# STM32G431RBT6.net
KiCad netlist of a schematic drawn in Altium Designer
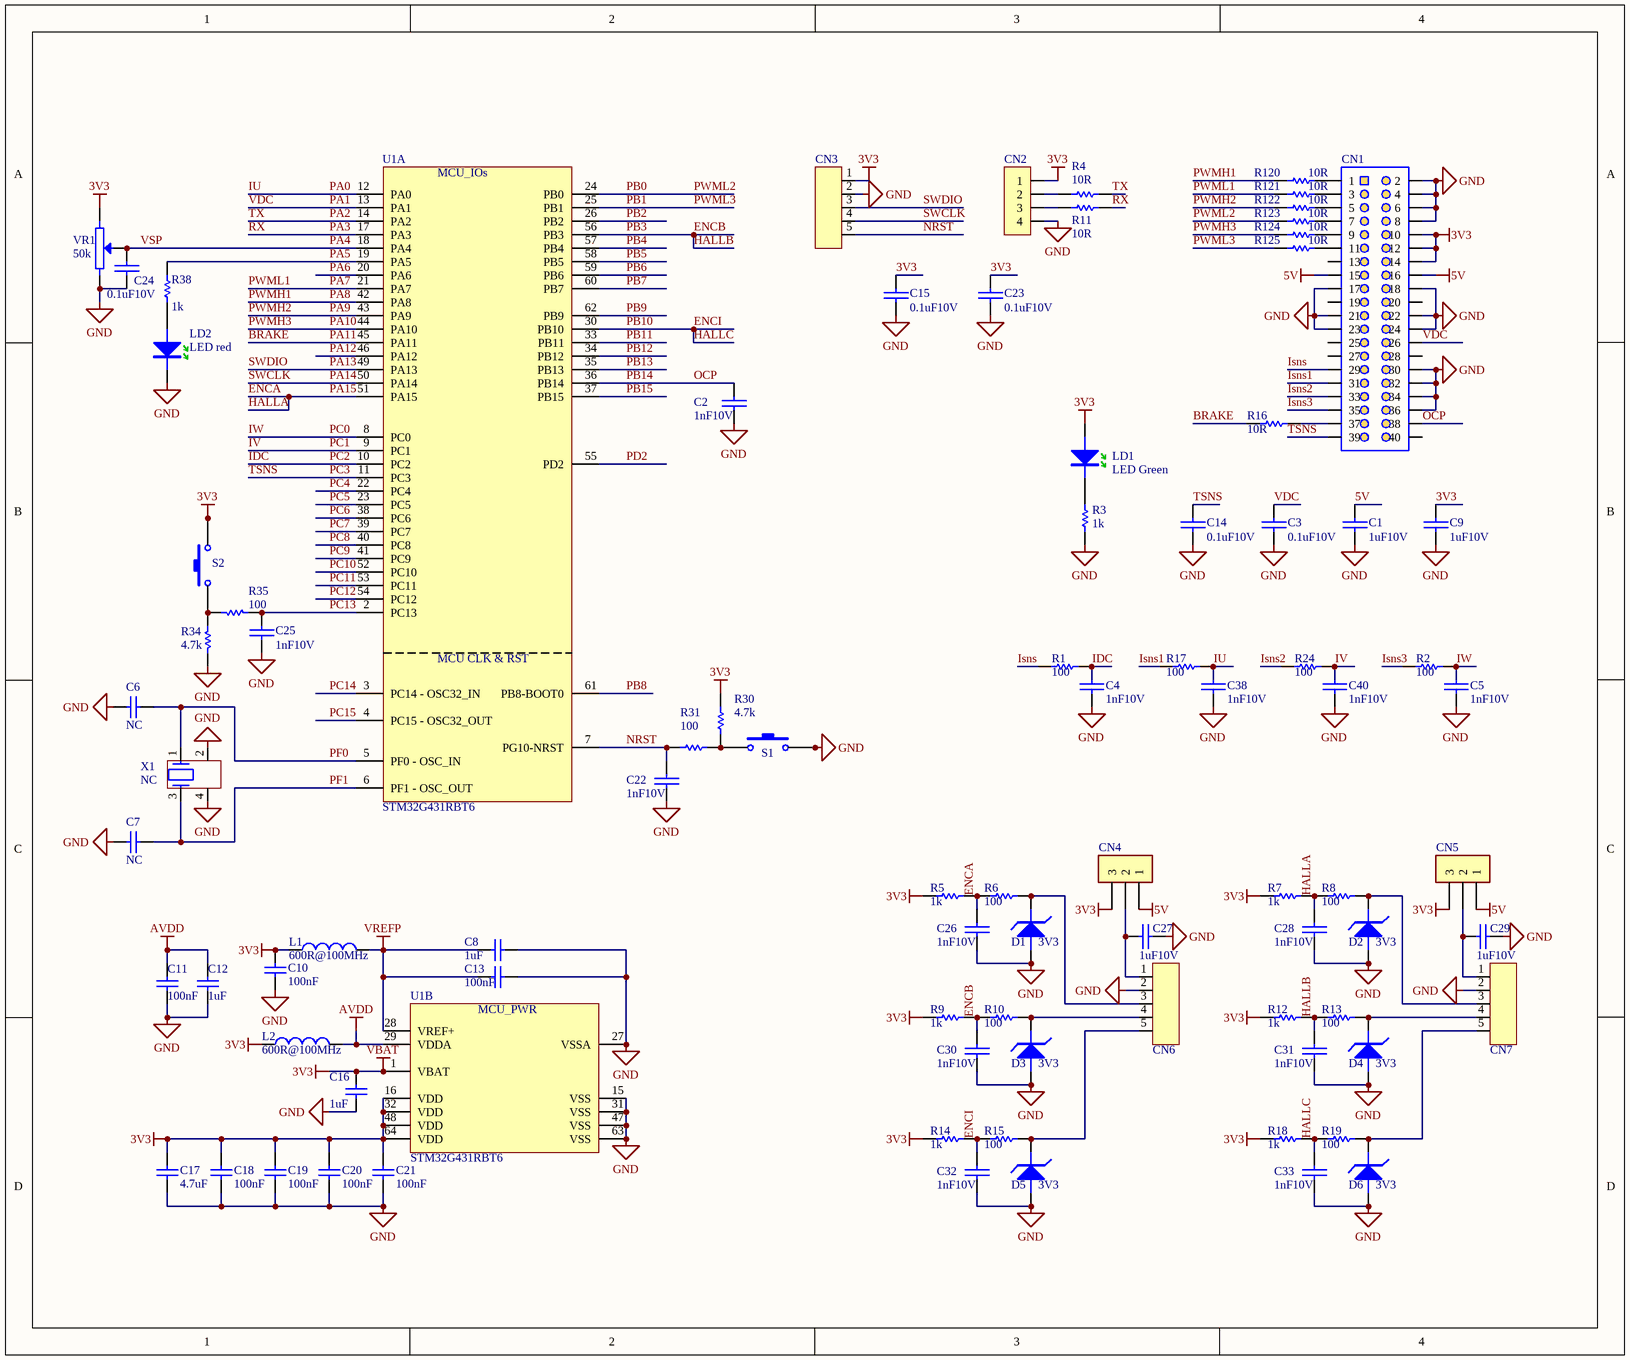
[diagram p0: STM32G431RBT6.SchDoc]

(export (version "E")
  (design (tool "Eeschema 10.0.6"))
  (components
    (comp (ref "C1")
      (value "UMK107AB7105KA-T")
      (footprint "CC0603")
      (fields
        (field (name "PART NUMBER") "C0603-10uF-50V-X7R-10%")
        (field (name "SCHDESCRIPT") "1uF10V")
        (field (name "VOLTAGE") "50")
        (field (name "TOLERANCE") "0.1")
      )
      (libsource (lib "EPC_Lib") (part "Capacitor-NonPolarized"))
    )
    (comp (ref "C2")
      (value "C0402C102J5GACTU")
      (footprint "CC0402")
      (fields
        (field (name "PART NUMBER") "C0402-1nF-50V-C0G/NP0-5%")
        (field (name "SCHDESCRIPT") "1nF10V")
        (field (name "EPC PART NUMBER") "C-0402-024")
        (field (name "VOLTAGE") "50")
      )
      (libsource (lib "EPC_Lib") (part "Capacitor-NonPolarized"))
    )
    (comp (ref "C3")
      (value "CC0402KRX7R8BB104")
      (footprint "CC0603")
      (fields
        (field (name "PART NUMBER") "C0402-100nF-25V-X7R-10%-Yaego")
        (field (name "SCHDESCRIPT") "0.1uF10V")
        (field (name "EPC PART NUMBER") "C-0402-088")
        (field (name "VOLTAGE") "25")
      )
      (libsource (lib "EPC_Lib") (part "Capacitor-NonPolarized"))
    )
    (comp (ref "C4")
      (value "C0402C102J5GACTU")
      (footprint "CC0402")
      (fields
        (field (name "PART NUMBER") "C0402-1nF-50V-C0G/NP0-5%")
        (field (name "SCHDESCRIPT") "1nF10V")
        (field (name "EPC PART NUMBER") "C-0402-024")
        (field (name "VOLTAGE") "50")
      )
      (libsource (lib "EPC_Lib") (part "Capacitor-NonPolarized"))
    )
    (comp (ref "C5")
      (value "C0402C102J5GACTU")
      (footprint "CC0402")
      (fields
        (field (name "PART NUMBER") "C0402-1nF-50V-C0G/NP0-5%")
        (field (name "SCHDESCRIPT") "1nF10V")
        (field (name "EPC PART NUMBER") "C-0402-024")
        (field (name "VOLTAGE") "50")
      )
      (libsource (lib "EPC_Lib") (part "Capacitor-NonPolarized"))
    )
    (comp (ref "C6")
      (value "NC")
      (footprint "CC0402")
      (description "Capacitor, MLCC, 6.8pF, 50V, NPO, +-0.25pF, 0402, T=0.5mm")
      (fields
        (field (name "INTERNAL_PART_NUMBER") "MCD-00674")
        (field (name "MANUFACTURER_PART_NUMBER") "CC0402CRNPO9BN6R8")
        (field (name "PROVIDED_BY") "SUBCO")
      )
      (libsource (lib "MCD_PARTS_database") (part "Capacitor"))
    )
    (comp (ref "C7")
      (value "NC")
      (footprint "CC0402")
      (description "Capacitor, MLCC, 6.8pF, 50V, NPO, +-0.25pF, 0402, T=0.5mm")
      (fields
        (field (name "INTERNAL_PART_NUMBER") "MCD-00674")
        (field (name "MANUFACTURER_PART_NUMBER") "CC0402CRNPO9BN6R8")
        (field (name "PROVIDED_BY") "SUBCO")
      )
      (libsource (lib "MCD_PARTS_database") (part "Capacitor"))
    )
    (comp (ref "C8")
      (value "1uF")
      (footprint "CC0603")
      (description "Capacitor, MLCC, 1uF, 16V, X5R, 10%, 0603, T=0,8mm")
      (fields
        (field (name "INTERNAL_PART_NUMBER") "MCD-00010")
        (field (name "MANUFACTURER_PART_NUMBER") "CC0603KRX5R7BB105")
        (field (name "PROVIDED_BY") "Subcon")
      )
      (libsource (lib "MCD_PARTS_database") (part "Capacitor"))
    )
    (comp (ref "C9")
      (value "UMK107AB7105KA-T")
      (footprint "CC0603")
      (fields
        (field (name "PART NUMBER") "C0603-10uF-50V-X7R-10%")
        (field (name "SCHDESCRIPT") "1uF10V")
        (field (name "VOLTAGE") "50")
        (field (name "TOLERANCE") "0.1")
      )
      (libsource (lib "EPC_Lib") (part "Capacitor-NonPolarized"))
    )
    (comp (ref "C10")
      (value "100nF")
      (footprint "CC0402")
      (description "Capacitor, MLCC, 100nF, 16V, X7R, 10%, 0402, T=0,5mm")
      (fields
        (field (name "INTERNAL_PART_NUMBER") "MCD-00102")
        (field (name "MANUFACTURER_PART_NUMBER") "CC0402KRX7R7BB104")
        (field (name "PROVIDED_BY") "Subcon")
      )
      (libsource (lib "MCD_PARTS_database") (part "Capacitor"))
    )
    (comp (ref "C11")
      (value "100nF")
      (footprint "CC0402")
      (description "Capacitor, MLCC, 100nF, 16V, X7R, 10%, 0402, T=0,5mm")
      (fields
        (field (name "INTERNAL_PART_NUMBER") "MCD-00102")
        (field (name "MANUFACTURER_PART_NUMBER") "CC0402KRX7R7BB104")
        (field (name "PROVIDED_BY") "Subcon")
      )
      (libsource (lib "MCD_PARTS_database") (part "Capacitor"))
    )
    (comp (ref "C12")
      (value "1uF")
      (footprint "CC0603")
      (description "Capacitor, MLCC, 1uF, 16V, X5R, 10%, 0603, T=0,8mm")
      (fields
        (field (name "INTERNAL_PART_NUMBER") "MCD-00010")
        (field (name "MANUFACTURER_PART_NUMBER") "CC0603KRX5R7BB105")
        (field (name "PROVIDED_BY") "Subcon")
      )
      (libsource (lib "MCD_PARTS_database") (part "Capacitor"))
    )
    (comp (ref "C13")
      (value "100nF")
      (footprint "CC0402")
      (description "Capacitor, MLCC, 100nF, 16V, X7R, 10%, 0402, T=0,5mm")
      (fields
        (field (name "INTERNAL_PART_NUMBER") "MCD-00102")
        (field (name "MANUFACTURER_PART_NUMBER") "CC0402KRX7R7BB104")
        (field (name "PROVIDED_BY") "Subcon")
      )
      (libsource (lib "MCD_PARTS_database") (part "Capacitor"))
    )
    (comp (ref "C14")
      (value "CC0402KRX7R8BB104")
      (footprint "CC0603")
      (fields
        (field (name "PART NUMBER") "C0402-100nF-25V-X7R-10%-Yaego")
        (field (name "SCHDESCRIPT") "0.1uF10V")
        (field (name "EPC PART NUMBER") "C-0402-088")
        (field (name "VOLTAGE") "25")
      )
      (libsource (lib "EPC_Lib") (part "Capacitor-NonPolarized"))
    )
    (comp (ref "C15")
      (value "CC0402KRX7R8BB104")
      (footprint "CC0402")
      (fields
        (field (name "PART NUMBER") "C0402-100nF-25V-X7R-10%-Yaego")
        (field (name "SCHDESCRIPT") "0.1uF10V")
        (field (name "EPC PART NUMBER") "C-0402-088")
        (field (name "VOLTAGE") "25")
      )
      (libsource (lib "EPC_Lib") (part "Capacitor-NonPolarized"))
    )
    (comp (ref "C16")
      (value "1uF")
      (footprint "CC0603")
      (description "Capacitor, MLCC, 1uF, 16V, X5R, 10%, 0603, T=0,8mm")
      (fields
        (field (name "INTERNAL_PART_NUMBER") "MCD-00010")
        (field (name "MANUFACTURER_PART_NUMBER") "CC0603KRX5R7BB105")
        (field (name "PROVIDED_BY") "Subcon")
      )
      (libsource (lib "MCD_PARTS_database") (part "Capacitor"))
    )
    (comp (ref "C17")
      (value "4.7uF")
      (footprint "CC0603")
      (description "Capacitor, MLCC, 4.7uF, 16V, X5R, 10%, 0603, T=0.8mm")
      (fields
        (field (name "INTERNAL_PART_NUMBER") "MCD-00009")
        (field (name "MANUFACTURER_PART_NUMBER") "CC0603KRX5R7BB475")
        (field (name "PROVIDED_BY") "subcon")
      )
      (libsource (lib "MCD_PARTS_database") (part "Capacitor"))
    )
    (comp (ref "C18")
      (value "100nF")
      (footprint "CC0402")
      (description "Capacitor, MLCC, 100nF, 16V, X7R, 10%, 0402, T=0,5mm")
      (fields
        (field (name "INTERNAL_PART_NUMBER") "MCD-00102")
        (field (name "MANUFACTURER_PART_NUMBER") "CC0402KRX7R7BB104")
        (field (name "PROVIDED_BY") "Subcon")
      )
      (libsource (lib "MCD_PARTS_database") (part "Capacitor"))
    )
    (comp (ref "C19")
      (value "100nF")
      (footprint "CC0402")
      (description "Capacitor, MLCC, 100nF, 16V, X7R, 10%, 0402, T=0,5mm")
      (fields
        (field (name "INTERNAL_PART_NUMBER") "MCD-00102")
        (field (name "MANUFACTURER_PART_NUMBER") "CC0402KRX7R7BB104")
        (field (name "PROVIDED_BY") "Subcon")
      )
      (libsource (lib "MCD_PARTS_database") (part "Capacitor"))
    )
    (comp (ref "C20")
      (value "100nF")
      (footprint "CC0402")
      (description "Capacitor, MLCC, 100nF, 16V, X7R, 10%, 0402, T=0,5mm")
      (fields
        (field (name "INTERNAL_PART_NUMBER") "MCD-00102")
        (field (name "MANUFACTURER_PART_NUMBER") "CC0402KRX7R7BB104")
        (field (name "PROVIDED_BY") "Subcon")
      )
      (libsource (lib "MCD_PARTS_database") (part "Capacitor"))
    )
    (comp (ref "C21")
      (value "100nF")
      (footprint "CC0402")
      (description "Capacitor, MLCC, 100nF, 16V, X7R, 10%, 0402, T=0,5mm")
      (fields
        (field (name "INTERNAL_PART_NUMBER") "MCD-00102")
        (field (name "MANUFACTURER_PART_NUMBER") "CC0402KRX7R7BB104")
        (field (name "PROVIDED_BY") "Subcon")
      )
      (libsource (lib "MCD_PARTS_database") (part "Capacitor"))
    )
    (comp (ref "C22")
      (value "CC0402KRX7R8BB104")
      (footprint "CC0402")
      (fields
        (field (name "PART NUMBER") "C0402-100nF-25V-X7R-10%-Yaego")
        (field (name "SCHDESCRIPT") "1nF10V")
        (field (name "EPC PART NUMBER") "C-0402-088")
        (field (name "VOLTAGE") "25")
      )
      (libsource (lib "EPC_Lib") (part "Capacitor-NonPolarized"))
    )
    (comp (ref "C23")
      (value "CC0402KRX7R8BB104")
      (footprint "CC0402")
      (fields
        (field (name "PART NUMBER") "C0402-100nF-25V-X7R-10%-Yaego")
        (field (name "SCHDESCRIPT") "0.1uF10V")
        (field (name "EPC PART NUMBER") "C-0402-088")
        (field (name "VOLTAGE") "25")
      )
      (libsource (lib "EPC_Lib") (part "Capacitor-NonPolarized"))
    )
    (comp (ref "C24")
      (value "CC0402KRX7R8BB104")
      (footprint "CC0402")
      (fields
        (field (name "PART NUMBER") "C0402-100nF-25V-X7R-10%-Yaego")
        (field (name "SCHDESCRIPT") "0.1uF10V")
        (field (name "EPC PART NUMBER") "C-0402-088")
        (field (name "VOLTAGE") "25")
      )
      (libsource (lib "EPC_Lib") (part "Capacitor-NonPolarized"))
    )
    (comp (ref "C25")
      (value "CC0402KRX7R8BB104")
      (footprint "CC0402")
      (fields
        (field (name "PART NUMBER") "C0402-100nF-25V-X7R-10%-Yaego")
        (field (name "SCHDESCRIPT") "1nF10V")
        (field (name "EPC PART NUMBER") "C-0402-088")
        (field (name "VOLTAGE") "25")
      )
      (libsource (lib "EPC_Lib") (part "Capacitor-NonPolarized"))
    )
    (comp (ref "C26")
      (value "C0402C102J5GACTU")
      (footprint "CC0402")
      (fields
        (field (name "PART NUMBER") "C0402-1nF-50V-C0G/NP0-5%")
        (field (name "SCHDESCRIPT") "1nF10V")
        (field (name "EPC PART NUMBER") "C-0402-024")
        (field (name "VOLTAGE") "50")
      )
      (libsource (lib "EPC_Lib") (part "Capacitor-NonPolarized"))
    )
    (comp (ref "C27")
      (value "1uF10V")
      (footprint "0603C")
      (fields (field (name "MFG") "TDK"))
      (libsource (lib "Personal") (part "CAP0603"))
    )
    (comp (ref "C28")
      (value "C0402C102J5GACTU")
      (footprint "CC0402")
      (fields
        (field (name "PART NUMBER") "C0402-1nF-50V-C0G/NP0-5%")
        (field (name "SCHDESCRIPT") "1nF10V")
        (field (name "EPC PART NUMBER") "C-0402-024")
        (field (name "VOLTAGE") "50")
      )
      (libsource (lib "EPC_Lib") (part "Capacitor-NonPolarized"))
    )
    (comp (ref "C29")
      (value "1uF10V")
      (footprint "0603C")
      (fields (field (name "MFG") "TDK"))
      (libsource (lib "Personal") (part "CAP0603"))
    )
    (comp (ref "C30")
      (value "C0402C102J5GACTU")
      (footprint "CC0402")
      (fields
        (field (name "PART NUMBER") "C0402-1nF-50V-C0G/NP0-5%")
        (field (name "SCHDESCRIPT") "1nF10V")
        (field (name "EPC PART NUMBER") "C-0402-024")
        (field (name "VOLTAGE") "50")
      )
      (libsource (lib "EPC_Lib") (part "Capacitor-NonPolarized"))
    )
    (comp (ref "C31")
      (value "C0402C102J5GACTU")
      (footprint "CC0402")
      (fields
        (field (name "PART NUMBER") "C0402-1nF-50V-C0G/NP0-5%")
        (field (name "SCHDESCRIPT") "1nF10V")
        (field (name "EPC PART NUMBER") "C-0402-024")
        (field (name "VOLTAGE") "50")
      )
      (libsource (lib "EPC_Lib") (part "Capacitor-NonPolarized"))
    )
    (comp (ref "C32")
      (value "C0402C102J5GACTU")
      (footprint "CC0402")
      (fields
        (field (name "PART NUMBER") "C0402-1nF-50V-C0G/NP0-5%")
        (field (name "SCHDESCRIPT") "1nF10V")
        (field (name "EPC PART NUMBER") "C-0402-024")
        (field (name "VOLTAGE") "50")
      )
      (libsource (lib "EPC_Lib") (part "Capacitor-NonPolarized"))
    )
    (comp (ref "C33")
      (value "C0402C102J5GACTU")
      (footprint "CC0402")
      (fields
        (field (name "PART NUMBER") "C0402-1nF-50V-C0G/NP0-5%")
        (field (name "SCHDESCRIPT") "1nF10V")
        (field (name "EPC PART NUMBER") "C-0402-024")
        (field (name "VOLTAGE") "50")
      )
      (libsource (lib "EPC_Lib") (part "Capacitor-NonPolarized"))
    )
    (comp (ref "C38")
      (value "C0402C102J5GACTU")
      (footprint "CC0402")
      (fields
        (field (name "PART NUMBER") "C0402-1nF-50V-C0G/NP0-5%")
        (field (name "SCHDESCRIPT") "1nF10V")
        (field (name "EPC PART NUMBER") "C-0402-024")
        (field (name "VOLTAGE") "50")
      )
      (libsource (lib "EPC_Lib") (part "Capacitor-NonPolarized"))
    )
    (comp (ref "C40")
      (value "C0402C102J5GACTU")
      (footprint "CC0402")
      (fields
        (field (name "PART NUMBER") "C0402-1nF-50V-C0G/NP0-5%")
        (field (name "SCHDESCRIPT") "1nF10V")
        (field (name "EPC PART NUMBER") "C-0402-024")
        (field (name "VOLTAGE") "50")
      )
      (libsource (lib "EPC_Lib") (part "Capacitor-NonPolarized"))
    )
    (comp (ref "CN1")
      (value "SFH11-PBPC-D17-ST-BK")
      (footprint "HDR_F10_D17_TH_VT_Pol_Bot")
      (description "34pin Female Vertical polarized on BOTTOM")
      (fields (field (name "MFG") "Sullins"))
      (libsource (lib "ATSAME70N20B") (part "HDR_F_D17_VT"))
    )
    (comp (ref "CN2")
      (value "~")
      (footprint "HDR_M10_S4_TH_VT")
      (libsource (lib "SERVO_EPC23101_ATSAME70N20B") (part "PIN-1-4-254"))
    )
    (comp (ref "CN3") (value "2.54mm,5Pin") (footprint "PIN5") (libsource (lib "F030") (part "PIN-1-5-254")))
    (comp (ref "CN4")
      (value "~")
      (footprint "PIN3_2.54mm")
      (description "CN")
      (libsource (lib "*") (part "CN3"))
    )
    (comp (ref "CN5")
      (value "~")
      (footprint "PIN3_2.54mm")
      (description "CN")
      (libsource (lib "*") (part "CN3"))
    )
    (comp (ref "CN6") (value "2.54mm,5Pin") (footprint "PIN5") (libsource (lib "") (part "PIN-1-5-254_1")))
    (comp (ref "CN7") (value "2.54mm,5Pin") (footprint "PIN5") (libsource (lib "") (part "PIN-1-5-254_1")))
    (comp (ref "D1")
      (value "3V3")
      (footprint "1206D")
      (description "Diode Zener")
      (fields (field (name "MFG") "Diodes Inc."))
      (libsource (lib "Personal") (part "Diode Zener"))
    )
    (comp (ref "D2")
      (value "3V3")
      (footprint "1206D")
      (description "Diode Zener")
      (fields (field (name "MFG") "Diodes Inc."))
      (libsource (lib "Personal") (part "Diode Zener"))
    )
    (comp (ref "D3")
      (value "3V3")
      (footprint "1206D")
      (description "Diode Zener")
      (fields (field (name "MFG") "Diodes Inc."))
      (libsource (lib "Personal") (part "Diode Zener"))
    )
    (comp (ref "D4")
      (value "3V3")
      (footprint "1206D")
      (description "Diode Zener")
      (fields (field (name "MFG") "Diodes Inc."))
      (libsource (lib "Personal") (part "Diode Zener"))
    )
    (comp (ref "D5")
      (value "3V3")
      (footprint "1206D")
      (description "Diode Zener")
      (fields (field (name "MFG") "Diodes Inc."))
      (libsource (lib "Personal") (part "Diode Zener"))
    )
    (comp (ref "D6")
      (value "3V3")
      (footprint "1206D")
      (description "Diode Zener")
      (fields (field (name "MFG") "Diodes Inc."))
      (libsource (lib "Personal") (part "Diode Zener"))
    )
    (comp (ref "L1")
      (value "600R@100MHz")
      (footprint "RC0603")
      (description "SMD Chip ferrite bead, 600R@100MHz +/-25%, 350mA, 500mohm DC, 0603, T=0.8mm")
      (fields
        (field (name "INTERNAL_PART_NUMBER") "MCD-00047")
        (field (name "MANUFACTURER_PART_NUMBER") "FCM1608KF-601T03")
        (field (name "PROVIDED_BY") "SUBCO")
      )
      (libsource (lib "MCD_PARTS_database") (part "BEAD"))
    )
    (comp (ref "L2")
      (value "600R@100MHz")
      (footprint "RC0603")
      (description "SMD Chip ferrite bead, 600R@100MHz +/-25%, 350mA, 500mohm DC, 0603, T=0.8mm")
      (fields
        (field (name "INTERNAL_PART_NUMBER") "MCD-00047")
        (field (name "MANUFACTURER_PART_NUMBER") "FCM1608KF-601T03")
        (field (name "PROVIDED_BY") "SUBCO")
      )
      (libsource (lib "MCD_PARTS_database") (part "BEAD"))
    )
    (comp (ref "LD1")
      (value "LED Green")
      (footprint "D0603")
      (description "Green 570nm LED Indication - Discrete 2V 0603")
      (fields (field (name "MFG") "Wurth") (field (name "Comment") "150060VS75000"))
      (libsource (lib "Personal") (part "LED0603Gn"))
    )
    (comp (ref "LD2")
      (value "LED red")
      (footprint "D0603")
      (description "Green 570nm LED Indication - Discrete 2V 0603")
      (fields (field (name "MFG") "Wurth") (field (name "Comment") "150060VS75000"))
      (libsource (lib "Personal") (part "LED0603Gn"))
    )
    (comp (ref "R1")
      (value "ERJ-2RKF1001X")
      (footprint "RC0402")
      (fields
        (field (name "PART NUMBER") "R0402-1k-1%-0.1W-Thickfilm")
        (field (name "SCHDESCRIPT") "100")
        (field (name "EPC PART NUMBER") "R-0402-020")
        (field (name "TOLERANCE") "0.01")
      )
      (libsource (lib "EPC_Lib") (part "Resistor"))
    )
    (comp (ref "R2")
      (value "ERJ-2RKF1001X")
      (footprint "RC0402")
      (fields
        (field (name "PART NUMBER") "R0402-1k-1%-0.1W-Thickfilm")
        (field (name "SCHDESCRIPT") "100")
        (field (name "EPC PART NUMBER") "R-0402-020")
        (field (name "TOLERANCE") "0.01")
      )
      (libsource (lib "EPC_Lib") (part "Resistor"))
    )
    (comp (ref "R3")
      (value "ERJ-2RKF1001X")
      (footprint "RC0402")
      (fields
        (field (name "PART NUMBER") "R0402-1k-1%-0.1W-Thickfilm")
        (field (name "SCHDESCRIPT") "1k")
        (field (name "EPC PART NUMBER") "R-0402-020")
        (field (name "TOLERANCE") "0.01")
      )
      (libsource (lib "EPC_Lib") (part "Resistor"))
    )
    (comp (ref "R4")
      (value "ERJ-2RKF1001X")
      (footprint "RC0402")
      (fields
        (field (name "PART NUMBER") "R0402-1k-1%-0.1W-Thickfilm")
        (field (name "SCHDESCRIPT") "10R")
        (field (name "EPC PART NUMBER") "R-0402-020")
        (field (name "TOLERANCE") "0.01")
      )
      (libsource (lib "EPC_Lib") (part "Resistor"))
    )
    (comp (ref "R5")
      (value "ERJ-2RKF1001X")
      (footprint "RC0402")
      (fields
        (field (name "PART NUMBER") "R0402-1k-1%-0.1W-Thickfilm")
        (field (name "SCHDESCRIPT") "1k")
        (field (name "EPC PART NUMBER") "R-0402-020")
        (field (name "TOLERANCE") "0.01")
      )
      (libsource (lib "EPC_Lib") (part "Resistor"))
    )
    (comp (ref "R6")
      (value "ERJ-2RKF1001X")
      (footprint "RC0402")
      (fields
        (field (name "PART NUMBER") "R0402-1k-1%-0.1W-Thickfilm")
        (field (name "SCHDESCRIPT") "100")
        (field (name "EPC PART NUMBER") "R-0402-020")
        (field (name "TOLERANCE") "0.01")
      )
      (libsource (lib "EPC_Lib") (part "Resistor"))
    )
    (comp (ref "R7")
      (value "ERJ-2RKF1001X")
      (footprint "RC0402")
      (fields
        (field (name "PART NUMBER") "R0402-1k-1%-0.1W-Thickfilm")
        (field (name "SCHDESCRIPT") "1k")
        (field (name "EPC PART NUMBER") "R-0402-020")
        (field (name "TOLERANCE") "0.01")
      )
      (libsource (lib "EPC_Lib") (part "Resistor"))
    )
    (comp (ref "R8")
      (value "ERJ-2RKF1001X")
      (footprint "RC0402")
      (fields
        (field (name "PART NUMBER") "R0402-1k-1%-0.1W-Thickfilm")
        (field (name "SCHDESCRIPT") "100")
        (field (name "EPC PART NUMBER") "R-0402-020")
        (field (name "TOLERANCE") "0.01")
      )
      (libsource (lib "EPC_Lib") (part "Resistor"))
    )
    (comp (ref "R9")
      (value "ERJ-2RKF1001X")
      (footprint "RC0402")
      (fields
        (field (name "PART NUMBER") "R0402-1k-1%-0.1W-Thickfilm")
        (field (name "SCHDESCRIPT") "1k")
        (field (name "EPC PART NUMBER") "R-0402-020")
        (field (name "TOLERANCE") "0.01")
      )
      (libsource (lib "EPC_Lib") (part "Resistor"))
    )
    (comp (ref "R10")
      (value "ERJ-2RKF1001X")
      (footprint "RC0402")
      (fields
        (field (name "PART NUMBER") "R0402-1k-1%-0.1W-Thickfilm")
        (field (name "SCHDESCRIPT") "100")
        (field (name "EPC PART NUMBER") "R-0402-020")
        (field (name "TOLERANCE") "0.01")
      )
      (libsource (lib "EPC_Lib") (part "Resistor"))
    )
    (comp (ref "R11")
      (value "ERJ-2RKF1001X")
      (footprint "RC0402")
      (fields
        (field (name "PART NUMBER") "R0402-1k-1%-0.1W-Thickfilm")
        (field (name "SCHDESCRIPT") "10R")
        (field (name "EPC PART NUMBER") "R-0402-020")
        (field (name "TOLERANCE") "0.01")
      )
      (libsource (lib "EPC_Lib") (part "Resistor"))
    )
    (comp (ref "R12")
      (value "ERJ-2RKF1001X")
      (footprint "RC0402")
      (fields
        (field (name "PART NUMBER") "R0402-1k-1%-0.1W-Thickfilm")
        (field (name "SCHDESCRIPT") "1k")
        (field (name "EPC PART NUMBER") "R-0402-020")
        (field (name "TOLERANCE") "0.01")
      )
      (libsource (lib "EPC_Lib") (part "Resistor"))
    )
    (comp (ref "R13")
      (value "ERJ-2RKF1001X")
      (footprint "RC0402")
      (fields
        (field (name "PART NUMBER") "R0402-1k-1%-0.1W-Thickfilm")
        (field (name "SCHDESCRIPT") "100")
        (field (name "EPC PART NUMBER") "R-0402-020")
        (field (name "TOLERANCE") "0.01")
      )
      (libsource (lib "EPC_Lib") (part "Resistor"))
    )
    (comp (ref "R14")
      (value "ERJ-2RKF1001X")
      (footprint "RC0402")
      (fields
        (field (name "PART NUMBER") "R0402-1k-1%-0.1W-Thickfilm")
        (field (name "SCHDESCRIPT") "1k")
        (field (name "EPC PART NUMBER") "R-0402-020")
        (field (name "TOLERANCE") "0.01")
      )
      (libsource (lib "EPC_Lib") (part "Resistor"))
    )
    (comp (ref "R15")
      (value "ERJ-2RKF1001X")
      (footprint "RC0402")
      (fields
        (field (name "PART NUMBER") "R0402-1k-1%-0.1W-Thickfilm")
        (field (name "SCHDESCRIPT") "100")
        (field (name "EPC PART NUMBER") "R-0402-020")
        (field (name "TOLERANCE") "0.01")
      )
      (libsource (lib "EPC_Lib") (part "Resistor"))
    )
    (comp (ref "R16")
      (value "ERJ-2RKF10R0X")
      (footprint "RC0402")
      (fields
        (field (name "PART NUMBER") "R0402-10-1%-0.1W-ThickFilm")
        (field (name "SCHDESCRIPT") "10R")
        (field (name "EPC PART NUMBER") "R-0402-015")
        (field (name "TOLERANCE") "0.01")
      )
      (libsource (lib "EPC_Lib") (part "Resistor"))
    )
    (comp (ref "R17")
      (value "ERJ-2RKF1001X")
      (footprint "RC0402")
      (fields
        (field (name "PART NUMBER") "R0402-1k-1%-0.1W-Thickfilm")
        (field (name "SCHDESCRIPT") "100")
        (field (name "EPC PART NUMBER") "R-0402-020")
        (field (name "TOLERANCE") "0.01")
      )
      (libsource (lib "EPC_Lib") (part "Resistor"))
    )
    (comp (ref "R18")
      (value "ERJ-2RKF1001X")
      (footprint "RC0402")
      (fields
        (field (name "PART NUMBER") "R0402-1k-1%-0.1W-Thickfilm")
        (field (name "SCHDESCRIPT") "1k")
        (field (name "EPC PART NUMBER") "R-0402-020")
        (field (name "TOLERANCE") "0.01")
      )
      (libsource (lib "EPC_Lib") (part "Resistor"))
    )
    (comp (ref "R19")
      (value "ERJ-2RKF1001X")
      (footprint "RC0402")
      (fields
        (field (name "PART NUMBER") "R0402-1k-1%-0.1W-Thickfilm")
        (field (name "SCHDESCRIPT") "100")
        (field (name "EPC PART NUMBER") "R-0402-020")
        (field (name "TOLERANCE") "0.01")
      )
      (libsource (lib "EPC_Lib") (part "Resistor"))
    )
    (comp (ref "R24")
      (value "ERJ-2RKF1001X")
      (footprint "RC0402")
      (fields
        (field (name "PART NUMBER") "R0402-1k-1%-0.1W-Thickfilm")
        (field (name "SCHDESCRIPT") "100")
        (field (name "EPC PART NUMBER") "R-0402-020")
        (field (name "TOLERANCE") "0.01")
      )
      (libsource (lib "EPC_Lib") (part "Resistor"))
    )
    (comp (ref "R30")
      (value "ERJ-2RKF1001X")
      (footprint "RC0402")
      (fields
        (field (name "PART NUMBER") "R0402-1k-1%-0.1W-Thickfilm")
        (field (name "SCHDESCRIPT") "4.7k")
        (field (name "EPC PART NUMBER") "R-0402-020")
        (field (name "TOLERANCE") "0.01")
      )
      (libsource (lib "EPC_Lib") (part "Resistor"))
    )
    (comp (ref "R31")
      (value "ERJ-2RKF1001X")
      (footprint "RC0402")
      (fields
        (field (name "PART NUMBER") "R0402-1k-1%-0.1W-Thickfilm")
        (field (name "SCHDESCRIPT") "100")
        (field (name "EPC PART NUMBER") "R-0402-020")
        (field (name "TOLERANCE") "0.01")
      )
      (libsource (lib "EPC_Lib") (part "Resistor"))
    )
    (comp (ref "R34")
      (value "ERJ-2RKF1001X")
      (footprint "RC0402")
      (fields
        (field (name "PART NUMBER") "R0402-1k-1%-0.1W-Thickfilm")
        (field (name "SCHDESCRIPT") "4.7k")
        (field (name "EPC PART NUMBER") "R-0402-020")
        (field (name "TOLERANCE") "0.01")
      )
      (libsource (lib "EPC_Lib") (part "Resistor"))
    )
    (comp (ref "R35")
      (value "ERJ-2RKF1001X")
      (footprint "RC0402")
      (fields
        (field (name "PART NUMBER") "R0402-1k-1%-0.1W-Thickfilm")
        (field (name "SCHDESCRIPT") "100")
        (field (name "EPC PART NUMBER") "R-0402-020")
        (field (name "TOLERANCE") "0.01")
      )
      (libsource (lib "EPC_Lib") (part "Resistor"))
    )
    (comp (ref "R38")
      (value "ERJ-2RKF1001X")
      (footprint "RC0402")
      (fields
        (field (name "PART NUMBER") "R0402-1k-1%-0.1W-Thickfilm")
        (field (name "SCHDESCRIPT") "1k")
        (field (name "EPC PART NUMBER") "R-0402-020")
        (field (name "TOLERANCE") "0.01")
      )
      (libsource (lib "EPC_Lib") (part "Resistor"))
    )
    (comp (ref "R120")
      (value "ERJ-2RKF10R0X")
      (footprint "RC0402")
      (fields
        (field (name "PART NUMBER") "R0402-10-1%-0.1W-ThickFilm")
        (field (name "SCHDESCRIPT") "10R")
        (field (name "EPC PART NUMBER") "R-0402-015")
        (field (name "TOLERANCE") "0.01")
      )
      (libsource (lib "EPC_Lib") (part "Resistor"))
    )
    (comp (ref "R121")
      (value "ERJ-2RKF10R0X")
      (footprint "RC0402")
      (fields
        (field (name "PART NUMBER") "R0402-10-1%-0.1W-ThickFilm")
        (field (name "SCHDESCRIPT") "10R")
        (field (name "EPC PART NUMBER") "R-0402-015")
        (field (name "TOLERANCE") "0.01")
      )
      (libsource (lib "EPC_Lib") (part "Resistor"))
    )
    (comp (ref "R122")
      (value "ERJ-2RKF10R0X")
      (footprint "RC0402")
      (fields
        (field (name "PART NUMBER") "R0402-10-1%-0.1W-ThickFilm")
        (field (name "SCHDESCRIPT") "10R")
        (field (name "EPC PART NUMBER") "R-0402-015")
        (field (name "TOLERANCE") "0.01")
      )
      (libsource (lib "EPC_Lib") (part "Resistor"))
    )
    (comp (ref "R123")
      (value "ERJ-2RKF10R0X")
      (footprint "RC0402")
      (fields
        (field (name "PART NUMBER") "R0402-10-1%-0.1W-ThickFilm")
        (field (name "SCHDESCRIPT") "10R")
        (field (name "EPC PART NUMBER") "R-0402-015")
        (field (name "TOLERANCE") "0.01")
      )
      (libsource (lib "EPC_Lib") (part "Resistor"))
    )
    (comp (ref "R124")
      (value "ERJ-2RKF10R0X")
      (footprint "RC0402")
      (fields
        (field (name "PART NUMBER") "R0402-10-1%-0.1W-ThickFilm")
        (field (name "SCHDESCRIPT") "10R")
        (field (name "EPC PART NUMBER") "R-0402-015")
        (field (name "TOLERANCE") "0.01")
      )
      (libsource (lib "EPC_Lib") (part "Resistor"))
    )
    (comp (ref "R125")
      (value "ERJ-2RKF10R0X")
      (footprint "RC0402")
      (fields
        (field (name "PART NUMBER") "R0402-10-1%-0.1W-ThickFilm")
        (field (name "SCHDESCRIPT") "10R")
        (field (name "EPC PART NUMBER") "R-0402-015")
        (field (name "TOLERANCE") "0.01")
      )
      (libsource (lib "EPC_Lib") (part "Resistor"))
    )
    (comp (ref "S1")
      (value "SW-PB")
      (footprint "B3S-1000-4_V")
      (description "Switch")
      (fields (field (name "PUBLISHER") "Altium Limited"))
      (libsource (lib "EPC21603") (part "SW-PB"))
    )
    (comp (ref "S2")
      (value "SW-PB")
      (footprint "B3S-1000-4_V")
      (description "Switch")
      (fields (field (name "PUBLISHER") "Altium Limited"))
      (libsource (lib "EPC21603") (part "SW-PB"))
    )
    (comp (ref "U1")
      (value "STM32G431RBT6")
      (footprint "ICC_LQFP64_10X10_P050_SOCKET_YAMAICHI_IC149-064-069-B5_NM")
      (description "STM32G474, LQFP64 package,?3D IC footprint with 2D socket footprint.")
      (fields
        (field (name "INTERNAL_PART_NUMBER") "MCD-01243")
        (field (name "MANUFACTURER_PART_NUMBER") "STM32G474RET6")
        (field (name "PROVIDED_BY") "SUBCO with ST control")
      )
      (libsource (lib "MCD_PARTS_database") (part "STM32G4xx_LQFP64"))
    )
    (comp (ref "VR1")
      (value "50k")
      (footprint "M63P")
      (description "Potentiometer")
      (libsource (lib "PCB_PROJECT1") (part "RES可调"))
    )
    (comp (ref "X1")
      (value "NC")
      (footprint "CRY_NX2016SA_4P")
      (description "Crystal 24MHz, 6pF, +-20ppm, 80ohms max, SMD")
      (fields
        (field (name "INTERNAL_PART_NUMBER") "MCD-01036")
        (field (name "MANUFACTURER_PART_NUMBER") "NX2016SA 24MHz EXS00A-CS10820")
        (field (name "PROVIDED_BY") "SUBCO")
      )
      (libsource (lib "MCD_PARTS_database") (part "XTAL_4_PINS"))
    )
  )
  (nets
    (net (code "1") (name "/BRAKE") (class "Default")
      (node (ref "R16") (pin "1") (pinfunction "1_1") (pintype "passive"))
      (node (ref "U1") (pin "45") (pinfunction "PA11_45") (pintype "passive"))
    )
    (net (code "2") (name "/ENCA") (class "Default")
      (node (ref "C26") (pin "1") (pinfunction "1_1") (pintype "passive"))
      (node (ref "C28") (pin "1") (pinfunction "1_1") (pintype "passive"))
      (node (ref "R5") (pin "2") (pinfunction "2_2") (pintype "passive"))
      (node (ref "R6") (pin "1") (pinfunction "1_1") (pintype "passive"))
      (node (ref "R7") (pin "2") (pinfunction "2_2") (pintype "passive"))
      (node (ref "R8") (pin "1") (pinfunction "1_1") (pintype "passive"))
      (node (ref "U1") (pin "51") (pinfunction "PA15_51") (pintype "passive"))
    )
    (net (code "3") (name "/ENCB") (class "Default")
      (node (ref "C30") (pin "1") (pinfunction "1_1") (pintype "passive"))
      (node (ref "C31") (pin "1") (pinfunction "1_1") (pintype "passive"))
      (node (ref "R10") (pin "1") (pinfunction "1_1") (pintype "passive"))
      (node (ref "R12") (pin "2") (pinfunction "2_2") (pintype "passive"))
      (node (ref "R13") (pin "1") (pinfunction "1_1") (pintype "passive"))
      (node (ref "R9") (pin "2") (pinfunction "2_2") (pintype "passive"))
      (node (ref "U1") (pin "56") (pinfunction "PB3_56") (pintype "passive"))
    )
    (net (code "4") (name "/ENCI") (class "Default")
      (node (ref "C32") (pin "1") (pinfunction "1_1") (pintype "passive"))
      (node (ref "C33") (pin "1") (pinfunction "1_1") (pintype "passive"))
      (node (ref "R14") (pin "2") (pinfunction "2_2") (pintype "passive"))
      (node (ref "R15") (pin "1") (pinfunction "1_1") (pintype "passive"))
      (node (ref "R18") (pin "2") (pinfunction "2_2") (pintype "passive"))
      (node (ref "R19") (pin "1") (pinfunction "1_1") (pintype "passive"))
      (node (ref "U1") (pin "30") (pinfunction "PB10_30") (pintype "passive"))
    )
    (net (code "5") (name "/IDC") (class "Default")
      (node (ref "C4") (pin "1") (pinfunction "1_1") (pintype "passive"))
      (node (ref "R1") (pin "2") (pinfunction "2_2") (pintype "passive"))
      (node (ref "U1") (pin "10") (pinfunction "PC2_10") (pintype "passive"))
    )
    (net (code "6") (name "/IU") (class "Default")
      (node (ref "C38") (pin "1") (pinfunction "1_1") (pintype "passive"))
      (node (ref "R17") (pin "2") (pinfunction "2_2") (pintype "passive"))
      (node (ref "U1") (pin "12") (pinfunction "PA0_12") (pintype "passive"))
    )
    (net (code "7") (name "/IV") (class "Default")
      (node (ref "C40") (pin "1") (pinfunction "1_1") (pintype "passive"))
      (node (ref "R24") (pin "2") (pinfunction "2_2") (pintype "passive"))
      (node (ref "U1") (pin "9") (pinfunction "PC1_9") (pintype "passive"))
    )
    (net (code "8") (name "/IW") (class "Default")
      (node (ref "C5") (pin "1") (pinfunction "1_1") (pintype "passive"))
      (node (ref "R2") (pin "2") (pinfunction "2_2") (pintype "passive"))
      (node (ref "U1") (pin "8") (pinfunction "PC0_8") (pintype "passive"))
    )
    (net (code "9") (name "/Isns") (class "Default")
      (node (ref "CN1") (pin "29") (pinfunction "29_29") (pintype "passive"))
      (node (ref "R1") (pin "1") (pinfunction "1_1") (pintype "passive"))
    )
    (net (code "10") (name "/Isns1") (class "Default")
      (node (ref "CN1") (pin "31") (pinfunction "31_31") (pintype "passive"))
      (node (ref "R17") (pin "1") (pinfunction "1_1") (pintype "passive"))
    )
    (net (code "11") (name "/Isns2") (class "Default")
      (node (ref "CN1") (pin "33") (pinfunction "33_33") (pintype "passive"))
      (node (ref "R24") (pin "1") (pinfunction "1_1") (pintype "passive"))
    )
    (net (code "12") (name "/Isns3") (class "Default")
      (node (ref "CN1") (pin "35") (pinfunction "35_35") (pintype "passive"))
      (node (ref "R2") (pin "1") (pinfunction "1_1") (pintype "passive"))
    )
    (net (code "13") (name "/NRST") (class "Default")
      (node (ref "C22") (pin "1") (pinfunction "1_1") (pintype "passive"))
      (node (ref "CN3") (pin "5") (pinfunction "5_5") (pintype "passive"))
      (node (ref "R31") (pin "2") (pinfunction "2_2") (pintype "passive"))
      (node (ref "U1") (pin "7") (pinfunction "PG10-NRST_7") (pintype "passive"))
    )
    (net (code "14") (name "/OCP") (class "Default")
      (node (ref "C2") (pin "1") (pinfunction "1_1") (pintype "passive"))
      (node (ref "CN1") (pin "38") (pinfunction "38_38") (pintype "passive"))
      (node (ref "U1") (pin "36") (pinfunction "PB14_36") (pintype "passive"))
    )
    (net (code "15") (name "/PA1") (class "Default")
      (node (ref "C3") (pin "1") (pinfunction "1_1") (pintype "passive"))
      (node (ref "CN1") (pin "26") (pinfunction "26_26") (pintype "passive"))
      (node (ref "U1") (pin "13") (pinfunction "PA1_13") (pintype "passive"))
    )
    (net (code "16") (name "/PA2") (class "Default")
      (node (ref "R4") (pin "1") (pinfunction "1_1") (pintype "passive"))
      (node (ref "U1") (pin "14") (pinfunction "PA2_14") (pintype "passive"))
    )
    (net (code "17") (name "/PA3") (class "Default")
      (node (ref "R11") (pin "1") (pinfunction "1_1") (pintype "passive"))
      (node (ref "U1") (pin "17") (pinfunction "PA3_17") (pintype "passive"))
    )
    (net (code "18") (name "/PA4") (class "Default")
      (node (ref "C24") (pin "1") (pinfunction "1_1") (pintype "passive"))
      (node (ref "U1") (pin "18") (pinfunction "PA4_18") (pintype "passive"))
      (node (ref "VR1") (pin "2") (pinfunction "2_2") (pintype "passive"))
    )
    (net (code "19") (name "/PA5") (class "Default")
      (node (ref "R38") (pin "2") (pinfunction "2_2") (pintype "passive"))
      (node (ref "U1") (pin "19") (pinfunction "PA5_19") (pintype "passive"))
    )
    (net (code "20") (name "/PA6") (class "Default")
      (node (ref "U1") (pin "20") (pinfunction "PA6_20") (pintype "passive"))
    )
    (net (code "21") (name "/PA7") (class "Default")
      (node (ref "R121") (pin "1") (pinfunction "1_1") (pintype "passive"))
      (node (ref "U1") (pin "21") (pinfunction "PA7_21") (pintype "passive"))
    )
    (net (code "22") (name "/PA8") (class "Default")
      (node (ref "R120") (pin "1") (pinfunction "1_1") (pintype "passive"))
      (node (ref "U1") (pin "42") (pinfunction "PA8_42") (pintype "passive"))
    )
    (net (code "23") (name "/PA9") (class "Default")
      (node (ref "R122") (pin "1") (pinfunction "1_1") (pintype "passive"))
      (node (ref "U1") (pin "43") (pinfunction "PA9_43") (pintype "passive"))
    )
    (net (code "24") (name "/PA10") (class "Default")
      (node (ref "R124") (pin "1") (pinfunction "1_1") (pintype "passive"))
      (node (ref "U1") (pin "44") (pinfunction "PA10_44") (pintype "passive"))
    )
    (net (code "25") (name "/PA12") (class "Default")
      (node (ref "U1") (pin "46") (pinfunction "PA12_46") (pintype "passive"))
    )
    (net (code "26") (name "/PA13") (class "Default")
      (node (ref "CN3") (pin "3") (pintype "passive"))
      (node (ref "U1") (pin "49") (pinfunction "PA13_49") (pintype "passive"))
    )
    (net (code "27") (name "/PA14") (class "Default")
      (node (ref "CN3") (pin "4") (pintype "passive"))
      (node (ref "U1") (pin "50") (pinfunction "PA14_50") (pintype "passive"))
    )
    (net (code "28") (name "/PB0") (class "Default")
      (node (ref "R123") (pin "1") (pinfunction "1_1") (pintype "passive"))
      (node (ref "U1") (pin "24") (pinfunction "PB0_24") (pintype "passive"))
    )
    (net (code "29") (name "/PB1") (class "Default")
      (node (ref "R125") (pin "1") (pinfunction "1_1") (pintype "passive"))
      (node (ref "U1") (pin "25") (pinfunction "PB1_25") (pintype "passive"))
    )
    (net (code "30") (name "/PB2") (class "Default")
      (node (ref "U1") (pin "26") (pinfunction "PB2_26") (pintype "passive"))
    )
    (net (code "31") (name "/PB4") (class "Default")
      (node (ref "U1") (pin "57") (pinfunction "PB4_57") (pintype "passive"))
    )
    (net (code "32") (name "/PB5") (class "Default")
      (node (ref "U1") (pin "58") (pinfunction "PB5_58") (pintype "passive"))
    )
    (net (code "33") (name "/PB6") (class "Default")
      (node (ref "U1") (pin "59") (pinfunction "PB6_59") (pintype "passive"))
    )
    (net (code "34") (name "/PB7") (class "Default")
      (node (ref "U1") (pin "60") (pinfunction "PB7_60") (pintype "passive"))
    )
    (net (code "35") (name "/PB8") (class "Default")
      (node (ref "U1") (pin "61") (pinfunction "PB8-BOOT0_61") (pintype "passive"))
    )
    (net (code "36") (name "/PB9") (class "Default")
      (node (ref "U1") (pin "62") (pinfunction "PB9_62") (pintype "passive"))
    )
    (net (code "37") (name "/PB11") (class "Default")
      (node (ref "U1") (pin "33") (pinfunction "PB11_33") (pintype "passive"))
    )
    (net (code "38") (name "/PB12") (class "Default")
      (node (ref "U1") (pin "34") (pinfunction "PB12_34") (pintype "passive"))
    )
    (net (code "39") (name "/PB13") (class "Default")
      (node (ref "U1") (pin "35") (pinfunction "PB13_35") (pintype "passive"))
    )
    (net (code "40") (name "/PB15") (class "Default")
      (node (ref "U1") (pin "37") (pinfunction "PB15_37") (pintype "passive"))
    )
    (net (code "41") (name "/PC3") (class "Default")
      (node (ref "C14") (pin "1") (pinfunction "1_1") (pintype "passive"))
      (node (ref "CN1") (pin "39") (pinfunction "39_39") (pintype "passive"))
      (node (ref "U1") (pin "11") (pinfunction "PC3_11") (pintype "passive"))
    )
    (net (code "42") (name "/PC4") (class "Default")
      (node (ref "U1") (pin "22") (pinfunction "PC4_22") (pintype "passive"))
    )
    (net (code "43") (name "/PC5") (class "Default")
      (node (ref "U1") (pin "23") (pinfunction "PC5_23") (pintype "passive"))
    )
    (net (code "44") (name "/PC6") (class "Default")
      (node (ref "U1") (pin "38") (pinfunction "PC6_38") (pintype "passive"))
    )
    (net (code "45") (name "/PC7") (class "Default")
      (node (ref "U1") (pin "39") (pinfunction "PC7_39") (pintype "passive"))
    )
    (net (code "46") (name "/PC8") (class "Default")
      (node (ref "U1") (pin "40") (pinfunction "PC8_40") (pintype "passive"))
    )
    (net (code "47") (name "/PC9") (class "Default")
      (node (ref "U1") (pin "41") (pinfunction "PC9_41") (pintype "passive"))
    )
    (net (code "48") (name "/PC10") (class "Default")
      (node (ref "U1") (pin "52") (pinfunction "PC10_52") (pintype "passive"))
    )
    (net (code "49") (name "/PC11") (class "Default")
      (node (ref "U1") (pin "53") (pinfunction "PC11_53") (pintype "passive"))
    )
    (net (code "50") (name "/PC12") (class "Default")
      (node (ref "U1") (pin "54") (pinfunction "PC12_54") (pintype "passive"))
    )
    (net (code "51") (name "/PC13") (class "Default")
      (node (ref "C25") (pin "1") (pinfunction "1_1") (pintype "passive"))
      (node (ref "R35") (pin "2") (pinfunction "2_2") (pintype "passive"))
      (node (ref "U1") (pin "2") (pinfunction "PC13_2") (pintype "passive"))
    )
    (net (code "52") (name "/PC14") (class "Default")
      (node (ref "U1") (pin "3") (pinfunction "PC14_-_OSC32_IN_3") (pintype "passive"))
    )
    (net (code "53") (name "/PC15") (class "Default")
      (node (ref "U1") (pin "4") (pinfunction "PC15_-_OSC32_OUT_4") (pintype "passive"))
    )
    (net (code "54") (name "/PD2") (class "Default")
      (node (ref "U1") (pin "55") (pinfunction "PD2_55") (pintype "passive"))
    )
    (net (code "55") (name "/PF0") (class "Default")
      (node (ref "C6") (pin "2") (pinfunction "2_2") (pintype "passive"))
      (node (ref "U1") (pin "5") (pinfunction "PF0_-_OSC_IN_5") (pintype "passive"))
      (node (ref "X1") (pin "1") (pinfunction "1_1") (pintype "passive"))
    )
    (net (code "56") (name "/PF1") (class "Default")
      (node (ref "C7") (pin "2") (pinfunction "2_2") (pintype "passive"))
      (node (ref "U1") (pin "6") (pinfunction "PF1_-_OSC_OUT_6") (pintype "passive"))
      (node (ref "X1") (pin "3") (pinfunction "3_3") (pintype "passive"))
    )
    (net (code "57") (name "3V3") (class "Default")
      (node (ref "C10") (pin "2") (pinfunction "2_2") (pintype "passive"))
      (node (ref "C15") (pin "1") (pinfunction "1_1") (pintype "passive"))
      (node (ref "C16") (pin "2") (pinfunction "2_2") (pintype "passive"))
      (node (ref "C17") (pin "2") (pinfunction "2_2") (pintype "passive"))
      (node (ref "C18") (pin "2") (pinfunction "2_2") (pintype "passive"))
      (node (ref "C19") (pin "2") (pinfunction "2_2") (pintype "passive"))
      (node (ref "C20") (pin "2") (pinfunction "2_2") (pintype "passive"))
      (node (ref "C21") (pin "2") (pinfunction "2_2") (pintype "passive"))
      (node (ref "C23") (pin "1") (pinfunction "1_1") (pintype "passive"))
      (node (ref "C9") (pin "1") (pinfunction "1_1") (pintype "passive"))
      (node (ref "CN1") (pin "10") (pinfunction "10_10") (pintype "passive"))
      (node (ref "CN1") (pin "12") (pinfunction "12_12") (pintype "passive"))
      (node (ref "CN1") (pin "14") (pinfunction "14_14") (pintype "passive"))
      (node (ref "CN2") (pin "1") (pinfunction "1_1") (pintype "passive"))
      (node (ref "CN3") (pin "1") (pintype "passive"))
      (node (ref "CN4") (pin "3") (pinfunction "3_3") (pintype "passive"))
      (node (ref "CN5") (pin "3") (pinfunction "3_3") (pintype "passive"))
      (node (ref "L1") (pin "1") (pinfunction "1_1") (pintype "passive"))
      (node (ref "L2") (pin "1") (pinfunction "1_1") (pintype "passive"))
      (node (ref "LD1") (pin "A") (pinfunction "A_A") (pintype "passive"))
      (node (ref "R12") (pin "1") (pinfunction "1_1") (pintype "passive"))
      (node (ref "R14") (pin "1") (pinfunction "1_1") (pintype "passive"))
      (node (ref "R18") (pin "1") (pinfunction "1_1") (pintype "passive"))
      (node (ref "R30") (pin "1") (pinfunction "1_1") (pintype "passive"))
      (node (ref "R5") (pin "1") (pinfunction "1_1") (pintype "passive"))
      (node (ref "R7") (pin "1") (pinfunction "1_1") (pintype "passive"))
      (node (ref "R9") (pin "1") (pinfunction "1_1") (pintype "passive"))
      (node (ref "S2") (pin "1") (pinfunction "1_1") (pintype "passive"))
      (node (ref "S2") (pin "2") (pinfunction "2_2") (pintype "passive"))
      (node (ref "U1") (pin "1") (pinfunction "VBAT_1") (pintype "passive"))
      (node (ref "U1") (pin "16") (pinfunction "VDD_16") (pintype "passive"))
      (node (ref "U1") (pin "32") (pinfunction "VDD_32") (pintype "passive"))
      (node (ref "U1") (pin "48") (pinfunction "VDD_48") (pintype "passive"))
      (node (ref "U1") (pin "64") (pinfunction "VDD_64") (pintype "passive"))
      (node (ref "VR1") (pin "1") (pinfunction "1_1") (pintype "passive"))
    )
    (net (code "58") (name "5V") (class "Default")
      (node (ref "C1") (pin "1") (pinfunction "1_1") (pintype "passive"))
      (node (ref "CN1") (pin "15") (pinfunction "15_15") (pintype "passive"))
      (node (ref "CN1") (pin "16") (pinfunction "16_16") (pintype "passive"))
      (node (ref "CN4") (pin "1") (pinfunction "1_1") (pintype "passive"))
      (node (ref "CN5") (pin "1") (pinfunction "1_1") (pintype "passive"))
    )
    (net (code "59") (name "AVDD") (class "Default")
      (node (ref "C11") (pin "2") (pinfunction "2_2") (pintype "passive"))
      (node (ref "C12") (pin "2") (pinfunction "2_2") (pintype "passive"))
      (node (ref "L2") (pin "2") (pinfunction "2_2") (pintype "passive"))
      (node (ref "U1") (pin "29") (pinfunction "VDDA_29") (pintype "passive"))
    )
    (net (code "60") (name "GND") (class "Default")
      (node (ref "C1") (pin "2") (pinfunction "2_2") (pintype "passive"))
      (node (ref "C10") (pin "1") (pinfunction "1_1") (pintype "passive"))
      (node (ref "C11") (pin "1") (pinfunction "1_1") (pintype "passive"))
      (node (ref "C12") (pin "1") (pinfunction "1_1") (pintype "passive"))
      (node (ref "C13") (pin "2") (pinfunction "2_2") (pintype "passive"))
      (node (ref "C14") (pin "2") (pinfunction "2_2") (pintype "passive"))
      (node (ref "C15") (pin "2") (pinfunction "2_2") (pintype "passive"))
      (node (ref "C16") (pin "1") (pinfunction "1_1") (pintype "passive"))
      (node (ref "C17") (pin "1") (pinfunction "1_1") (pintype "passive"))
      (node (ref "C18") (pin "1") (pinfunction "1_1") (pintype "passive"))
      (node (ref "C19") (pin "1") (pinfunction "1_1") (pintype "passive"))
      (node (ref "C2") (pin "2") (pinfunction "2_2") (pintype "passive"))
      (node (ref "C20") (pin "1") (pinfunction "1_1") (pintype "passive"))
      (node (ref "C21") (pin "1") (pinfunction "1_1") (pintype "passive"))
      (node (ref "C22") (pin "2") (pinfunction "2_2") (pintype "passive"))
      (node (ref "C23") (pin "2") (pinfunction "2_2") (pintype "passive"))
      (node (ref "C24") (pin "2") (pinfunction "2_2") (pintype "passive"))
      (node (ref "C25") (pin "2") (pinfunction "2_2") (pintype "passive"))
      (node (ref "C26") (pin "2") (pinfunction "2_2") (pintype "passive"))
      (node (ref "C27") (pin "2") (pinfunction "2_2") (pintype "passive"))
      (node (ref "C28") (pin "2") (pinfunction "2_2") (pintype "passive"))
      (node (ref "C29") (pin "2") (pinfunction "2_2") (pintype "passive"))
      (node (ref "C3") (pin "2") (pinfunction "2_2") (pintype "passive"))
      (node (ref "C30") (pin "2") (pinfunction "2_2") (pintype "passive"))
      (node (ref "C31") (pin "2") (pinfunction "2_2") (pintype "passive"))
      (node (ref "C32") (pin "2") (pinfunction "2_2") (pintype "passive"))
      (node (ref "C33") (pin "2") (pinfunction "2_2") (pintype "passive"))
      (node (ref "C38") (pin "2") (pinfunction "2_2") (pintype "passive"))
      (node (ref "C4") (pin "2") (pinfunction "2_2") (pintype "passive"))
      (node (ref "C40") (pin "2") (pinfunction "2_2") (pintype "passive"))
      (node (ref "C5") (pin "2") (pinfunction "2_2") (pintype "passive"))
      (node (ref "C6") (pin "1") (pinfunction "1_1") (pintype "passive"))
      (node (ref "C7") (pin "1") (pinfunction "1_1") (pintype "passive"))
      (node (ref "C8") (pin "2") (pinfunction "2_2") (pintype "passive"))
      (node (ref "C9") (pin "2") (pinfunction "2_2") (pintype "passive"))
      (node (ref "CN1") (pin "17") (pinfunction "17_17") (pintype "passive"))
      (node (ref "CN1") (pin "18") (pinfunction "18_18") (pintype "passive"))
      (node (ref "CN1") (pin "2") (pinfunction "2_2") (pintype "passive"))
      (node (ref "CN1") (pin "21") (pinfunction "21_21") (pintype "passive"))
      (node (ref "CN1") (pin "22") (pinfunction "22_22") (pintype "passive"))
      (node (ref "CN1") (pin "23") (pinfunction "23_23") (pintype "passive"))
      (node (ref "CN1") (pin "24") (pinfunction "24_24") (pintype "passive"))
      (node (ref "CN1") (pin "30") (pinfunction "30_30") (pintype "passive"))
      (node (ref "CN1") (pin "32") (pinfunction "32_32") (pintype "passive"))
      (node (ref "CN1") (pin "34") (pinfunction "34_34") (pintype "passive"))
      (node (ref "CN1") (pin "36") (pinfunction "36_36") (pintype "passive"))
      (node (ref "CN1") (pin "4") (pinfunction "4_4") (pintype "passive"))
      (node (ref "CN1") (pin "6") (pinfunction "6_6") (pintype "passive"))
      (node (ref "CN1") (pin "8") (pinfunction "8_8") (pintype "passive"))
      (node (ref "CN2") (pin "4") (pinfunction "4_4") (pintype "passive"))
      (node (ref "CN3") (pin "2") (pintype "passive"))
      (node (ref "CN6") (pin "2") (pintype "passive"))
      (node (ref "CN7") (pin "2") (pintype "passive"))
      (node (ref "D1") (pin "1") (pinfunction "A_1") (pintype "passive"))
      (node (ref "D2") (pin "1") (pinfunction "A_1") (pintype "passive"))
      (node (ref "D3") (pin "1") (pinfunction "A_1") (pintype "passive"))
      (node (ref "D4") (pin "1") (pinfunction "A_1") (pintype "passive"))
      (node (ref "D5") (pin "1") (pinfunction "A_1") (pintype "passive"))
      (node (ref "D6") (pin "1") (pinfunction "A_1") (pintype "passive"))
      (node (ref "LD2") (pin "K") (pinfunction "K_K") (pintype "passive"))
      (node (ref "R3") (pin "1") (pinfunction "1_1") (pintype "passive"))
      (node (ref "R34") (pin "2") (pinfunction "2_2") (pintype "passive"))
      (node (ref "S1") (pin "3") (pinfunction "3_3") (pintype "passive"))
      (node (ref "S1") (pin "4") (pinfunction "4_4") (pintype "passive"))
      (node (ref "U1") (pin "15") (pinfunction "VSS_15") (pintype "passive"))
      (node (ref "U1") (pin "27") (pinfunction "VSSA_27") (pintype "passive"))
      (node (ref "U1") (pin "31") (pinfunction "VSS_31") (pintype "passive"))
      (node (ref "U1") (pin "47") (pinfunction "VSS_47") (pintype "passive"))
      (node (ref "U1") (pin "63") (pinfunction "VSS_63") (pintype "passive"))
      (node (ref "VR1") (pin "3") (pinfunction "3_3") (pintype "passive"))
      (node (ref "X1") (pin "2") (pinfunction "2_2") (pintype "passive"))
      (node (ref "X1") (pin "4") (pinfunction "4_4") (pintype "passive"))
    )
    (net (code "61") (name "Net-(C27-Pad1)") (class "Default")
      (node (ref "C27") (pin "1") (pinfunction "1_1") (pintype "passive"))
      (node (ref "CN4") (pin "2") (pinfunction "2_2") (pintype "passive"))
      (node (ref "CN6") (pin "1") (pintype "passive"))
    )
    (net (code "62") (name "Net-(C29-Pad1)") (class "Default")
      (node (ref "C29") (pin "1") (pinfunction "1_1") (pintype "passive"))
      (node (ref "CN5") (pin "2") (pinfunction "2_2") (pintype "passive"))
      (node (ref "CN7") (pin "1") (pintype "passive"))
    )
    (net (code "63") (name "Net-(CN1-Pad1)") (class "Default")
      (node (ref "CN1") (pin "1") (pinfunction "1_1") (pintype "passive"))
      (node (ref "R120") (pin "2") (pinfunction "2_2") (pintype "passive"))
    )
    (net (code "64") (name "Net-(CN1-Pad3)") (class "Default")
      (node (ref "CN1") (pin "3") (pinfunction "3_3") (pintype "passive"))
      (node (ref "R121") (pin "2") (pinfunction "2_2") (pintype "passive"))
    )
    (net (code "65") (name "Net-(CN1-Pad5)") (class "Default")
      (node (ref "CN1") (pin "5") (pinfunction "5_5") (pintype "passive"))
      (node (ref "R122") (pin "2") (pinfunction "2_2") (pintype "passive"))
    )
    (net (code "66") (name "Net-(CN1-Pad7)") (class "Default")
      (node (ref "CN1") (pin "7") (pinfunction "7_7") (pintype "passive"))
      (node (ref "R123") (pin "2") (pinfunction "2_2") (pintype "passive"))
    )
    (net (code "67") (name "Net-(CN1-Pad9)") (class "Default")
      (node (ref "CN1") (pin "9") (pinfunction "9_9") (pintype "passive"))
      (node (ref "R124") (pin "2") (pinfunction "2_2") (pintype "passive"))
    )
    (net (code "68") (name "Net-(CN1-Pad11)") (class "Default")
      (node (ref "CN1") (pin "11") (pinfunction "11_11") (pintype "passive"))
      (node (ref "R125") (pin "2") (pinfunction "2_2") (pintype "passive"))
    )
    (net (code "69") (name "Net-(CN1-Pad37)") (class "Default")
      (node (ref "CN1") (pin "37") (pinfunction "37_37") (pintype "passive"))
      (node (ref "R16") (pin "2") (pinfunction "2_2") (pintype "passive"))
    )
    (net (code "70") (name "Net-(CN2-Pad2)") (class "Default")
      (node (ref "CN2") (pin "2") (pinfunction "2_2") (pintype "passive"))
      (node (ref "R4") (pin "2") (pinfunction "2_2") (pintype "passive"))
    )
    (net (code "71") (name "Net-(CN2-Pad3)") (class "Default")
      (node (ref "CN2") (pin "3") (pinfunction "3_3") (pintype "passive"))
      (node (ref "R11") (pin "2") (pinfunction "2_2") (pintype "passive"))
    )
    (net (code "72") (name "Net-(D1-K)") (class "Default")
      (node (ref "CN6") (pin "3") (pintype "passive"))
      (node (ref "D1") (pin "2") (pinfunction "K_2") (pintype "passive"))
      (node (ref "R6") (pin "2") (pinfunction "2_2") (pintype "passive"))
    )
    (net (code "73") (name "Net-(D2-K)") (class "Default")
      (node (ref "CN7") (pin "3") (pintype "passive"))
      (node (ref "D2") (pin "2") (pinfunction "K_2") (pintype "passive"))
      (node (ref "R8") (pin "2") (pinfunction "2_2") (pintype "passive"))
    )
    (net (code "74") (name "Net-(D3-K)") (class "Default")
      (node (ref "CN6") (pin "4") (pintype "passive"))
      (node (ref "D3") (pin "2") (pinfunction "K_2") (pintype "passive"))
      (node (ref "R10") (pin "2") (pinfunction "2_2") (pintype "passive"))
    )
    (net (code "75") (name "Net-(D4-K)") (class "Default")
      (node (ref "CN7") (pin "4") (pintype "passive"))
      (node (ref "D4") (pin "2") (pinfunction "K_2") (pintype "passive"))
      (node (ref "R13") (pin "2") (pinfunction "2_2") (pintype "passive"))
    )
    (net (code "76") (name "Net-(D5-K)") (class "Default")
      (node (ref "CN6") (pin "5") (pinfunction "5_5") (pintype "passive"))
      (node (ref "D5") (pin "2") (pinfunction "K_2") (pintype "passive"))
      (node (ref "R15") (pin "2") (pinfunction "2_2") (pintype "passive"))
    )
    (net (code "77") (name "Net-(D6-K)") (class "Default")
      (node (ref "CN7") (pin "5") (pinfunction "5_5") (pintype "passive"))
      (node (ref "D6") (pin "2") (pinfunction "K_2") (pintype "passive"))
      (node (ref "R19") (pin "2") (pinfunction "2_2") (pintype "passive"))
    )
    (net (code "78") (name "Net-(LD1-PadK)") (class "Default")
      (node (ref "LD1") (pin "K") (pinfunction "K_K") (pintype "passive"))
      (node (ref "R3") (pin "2") (pinfunction "2_2") (pintype "passive"))
    )
    (net (code "79") (name "Net-(LD2-PadA)") (class "Default")
      (node (ref "LD2") (pin "A") (pinfunction "A_A") (pintype "passive"))
      (node (ref "R38") (pin "1") (pinfunction "1_1") (pintype "passive"))
    )
    (net (code "80") (name "Net-(R30-Pad2)") (class "Default")
      (node (ref "R30") (pin "2") (pinfunction "2_2") (pintype "passive"))
      (node (ref "R31") (pin "1") (pinfunction "1_1") (pintype "passive"))
      (node (ref "S1") (pin "1") (pinfunction "1_1") (pintype "passive"))
      (node (ref "S1") (pin "2") (pinfunction "2_2") (pintype "passive"))
    )
    (net (code "81") (name "Net-(R34-Pad1)") (class "Default")
      (node (ref "R34") (pin "1") (pinfunction "1_1") (pintype "passive"))
      (node (ref "R35") (pin "1") (pinfunction "1_1") (pintype "passive"))
      (node (ref "S2") (pin "3") (pinfunction "3_3") (pintype "passive"))
      (node (ref "S2") (pin "4") (pinfunction "4_4") (pintype "passive"))
    )
    (net (code "82") (name "VREFP") (class "Default")
      (node (ref "C13") (pin "1") (pinfunction "1_1") (pintype "passive"))
      (node (ref "C8") (pin "1") (pinfunction "1_1") (pintype "passive"))
      (node (ref "L1") (pin "2") (pinfunction "2_2") (pintype "passive"))
      (node (ref "U1") (pin "28") (pinfunction "VREF+_28") (pintype "passive"))
    )
    (net (code "83") (name "unconnected-(CN1-Pad13)") (class "Default")
      (node (ref "CN1") (pin "13") (pinfunction "13_13") (pintype "passive"))
    )
    (net (code "84") (name "unconnected-(CN1-Pad19)") (class "Default")
      (node (ref "CN1") (pin "19") (pinfunction "19_19") (pintype "passive"))
    )
    (net (code "85") (name "unconnected-(CN1-Pad20)") (class "Default")
      (node (ref "CN1") (pin "20") (pinfunction "20_20") (pintype "passive"))
    )
    (net (code "86") (name "unconnected-(CN1-Pad25)") (class "Default")
      (node (ref "CN1") (pin "25") (pinfunction "25_25") (pintype "passive"))
    )
    (net (code "87") (name "unconnected-(CN1-Pad27)") (class "Default")
      (node (ref "CN1") (pin "27") (pinfunction "27_27") (pintype "passive"))
    )
    (net (code "88") (name "unconnected-(CN1-Pad28)") (class "Default")
      (node (ref "CN1") (pin "28") (pinfunction "28_28") (pintype "passive"))
    )
    (net (code "89") (name "unconnected-(CN1-Pad40)") (class "Default")
      (node (ref "CN1") (pin "40") (pinfunction "40_40") (pintype "passive"))
    )
  )
)
